# Driver5.net
KiCad netlist of a schematic drawn in Altium Designer
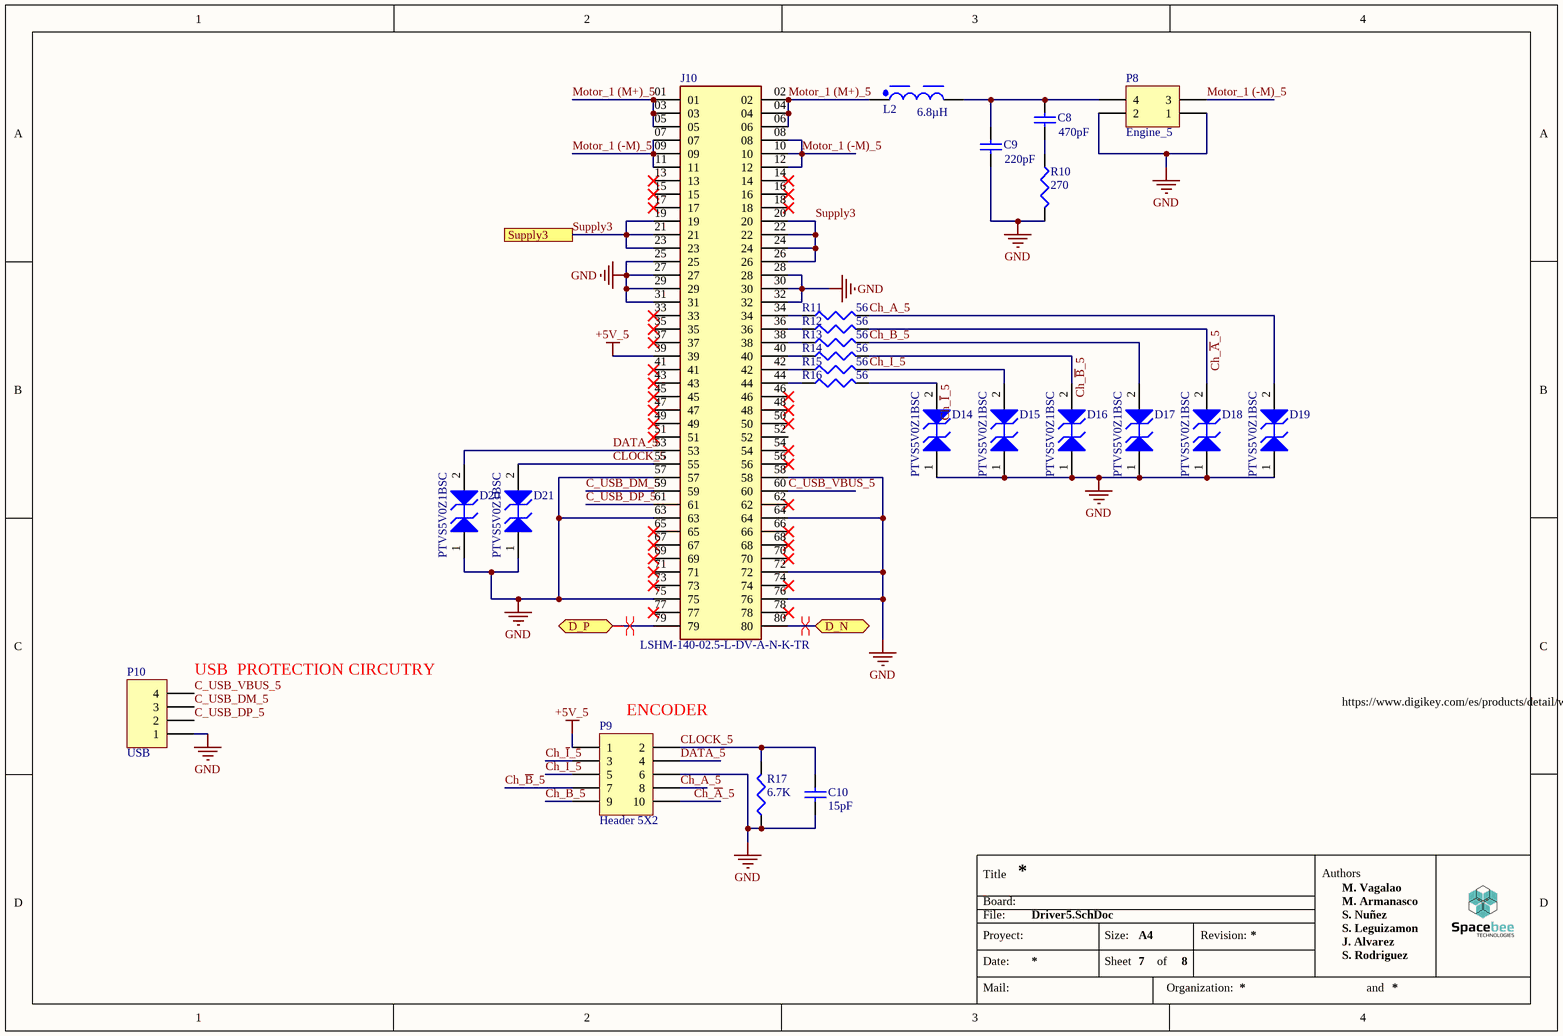
[diagram p0: Driver5.SchDoc]

(export (version "E")
  (design (tool "Eeschema 10.0.6"))
  (components
    (comp (ref "C8")
      (value "470pF")
      (footprint "1608[0603]")
      (description "Capacitor (Semiconductor SIM Model)")
      (fields (field (name "Comment") "Cap Semi") (field (name "PUBLISHER") "Altium Limited"))
      (libsource (lib "Miscellaneous Devices") (part "Cap Semi"))
    )
    (comp (ref "C9")
      (value "220pF")
      (footprint "1608[0603]")
      (description "Capacitor (Semiconductor SIM Model)")
      (fields (field (name "Comment") "Cap Semi") (field (name "PUBLISHER") "Altium Limited"))
      (libsource (lib "Miscellaneous Devices") (part "Cap Semi"))
    )
    (comp (ref "C10")
      (value "15pF")
      (footprint "6-0805_L")
      (description "Capacitor (Semiconductor SIM Model)")
      (fields (field (name "Comment") "Cap Semi") (field (name "PUBLISHER") "Altium Limited"))
      (libsource (lib "SpaceBee") (part "Cap 0805"))
    )
    (comp (ref "D14")
      (value "PTVS5V0Z1BSC")
      (footprint "SOD993B")
      (fields (field (name "MANUFACTURER") "On Semiconductor") (field (name "PARTNUMBER") "1SMB16CAT3"))
      (libsource (lib "DriverLib") (part "PTVS5V0Z1BSC"))
    )
    (comp (ref "D15")
      (value "PTVS5V0Z1BSC")
      (footprint "SOD993B")
      (fields (field (name "MANUFACTURER") "On Semiconductor") (field (name "PARTNUMBER") "1SMB16CAT3"))
      (libsource (lib "DriverLib") (part "PTVS5V0Z1BSC"))
    )
    (comp (ref "D16")
      (value "PTVS5V0Z1BSC")
      (footprint "SOD993B")
      (fields (field (name "MANUFACTURER") "On Semiconductor") (field (name "PARTNUMBER") "1SMB16CAT3"))
      (libsource (lib "DriverLib") (part "PTVS5V0Z1BSC"))
    )
    (comp (ref "D17")
      (value "PTVS5V0Z1BSC")
      (footprint "SOD993B")
      (fields (field (name "MANUFACTURER") "On Semiconductor") (field (name "PARTNUMBER") "1SMB16CAT3"))
      (libsource (lib "DriverLib") (part "PTVS5V0Z1BSC"))
    )
    (comp (ref "D18")
      (value "PTVS5V0Z1BSC")
      (footprint "SOD993B")
      (fields (field (name "MANUFACTURER") "On Semiconductor") (field (name "PARTNUMBER") "1SMB16CAT3"))
      (libsource (lib "DriverLib") (part "PTVS5V0Z1BSC"))
    )
    (comp (ref "D19")
      (value "PTVS5V0Z1BSC")
      (footprint "SOD993B")
      (fields (field (name "MANUFACTURER") "On Semiconductor") (field (name "PARTNUMBER") "1SMB16CAT3"))
      (libsource (lib "DriverLib") (part "PTVS5V0Z1BSC"))
    )
    (comp (ref "D20")
      (value "PTVS5V0Z1BSC")
      (footprint "SOD993B")
      (fields (field (name "MANUFACTURER") "On Semiconductor") (field (name "PARTNUMBER") "1SMB16CAT3"))
      (libsource (lib "DriverLib") (part "PTVS5V0Z1BSC"))
    )
    (comp (ref "D21")
      (value "PTVS5V0Z1BSC")
      (footprint "SOD993B")
      (fields (field (name "MANUFACTURER") "On Semiconductor") (field (name "PARTNUMBER") "1SMB16CAT3"))
      (libsource (lib "DriverLib") (part "PTVS5V0Z1BSC"))
    )
    (comp (ref "J10")
      (value "LSHM-140-02.5-L-DV-A-N-K-TR")
      (footprint "SAMTEC_LSHM-140-02.5-L-DV-A-N-K-TR")
      (description "LSHM - Samtec 0.50mm Razor Beam High-Speed Hermaphroditic Terminal / Socket Strip.")
      (libsource (lib "DriverLib") (part "LSHM-140-02.5-L-DV-A-N-K-TR"))
    )
    (comp (ref "L2")
      (value "6.8µH")
      (footprint "WE-XHMA_6060")
      (description "WE-XHMA SMD Power Inductor, size 1090, 6.8µH, 10.5A, 7.16mΩ")
      (fields
        (field (name "MANUFACTURER PART NUMBER") "78439369068")
        (field (name "MANUFACTURER") "Wurth Elektronik")
      )
      (libsource (lib "DriverLib") (part "78439369068"))
    )
    (comp (ref "P8")
      (value "Engine_5")
      (footprint "MOLEX_1724480004")
      (description "Header, 2-Pin, Dual row")
      (fields (field (name "PUBLISHER") "Altium Limited"))
      (libsource (lib "SpaceBee") (part "Header 2X2"))
    )
    (comp (ref "P9")
      (value "Header 5X2")
      (footprint "CONN_HIF3FC-14PA-2.54DS(71)_HIR")
      (description "Header, 5-Pin, Dual row")
      (fields (field (name "PUBLISHER") "Altium Limited"))
      (libsource (lib "DriverLib") (part "Header 5X2"))
    )
    (comp (ref "P10")
      (value "USB")
      (footprint "Header 4 SMD")
      (description "Header, 4-Pin")
      (fields (field (name "PUBLISHER") "Altium Limited"))
      (libsource (lib "SpaceBee") (part "Header 4 SMD"))
    )
    (comp (ref "R10")
      (value "270")
      (footprint "J1-0603")
      (description "Resistor")
      (fields (field (name "Comment") "Res3") (field (name "PUBLISHER") "Altium Limited"))
      (libsource (lib "Miscellaneous Devices") (part "Res3"))
    )
    (comp (ref "R11")
      (value "56")
      (footprint "J1-0603")
      (description "Resistor")
      (fields (field (name "Comment") "Res3") (field (name "PUBLISHER") "Altium Limited"))
      (libsource (lib "Miscellaneous Devices") (part "Res3"))
    )
    (comp (ref "R12")
      (value "56")
      (footprint "J1-0603")
      (description "Resistor")
      (fields (field (name "Comment") "Res3") (field (name "PUBLISHER") "Altium Limited"))
      (libsource (lib "Miscellaneous Devices") (part "Res3"))
    )
    (comp (ref "R13")
      (value "56")
      (footprint "J1-0603")
      (description "Resistor")
      (fields (field (name "Comment") "Res3") (field (name "PUBLISHER") "Altium Limited"))
      (libsource (lib "Miscellaneous Devices") (part "Res3"))
    )
    (comp (ref "R14")
      (value "56")
      (footprint "J1-0603")
      (description "Resistor")
      (fields (field (name "Comment") "Res3") (field (name "PUBLISHER") "Altium Limited"))
      (libsource (lib "Miscellaneous Devices") (part "Res3"))
    )
    (comp (ref "R15")
      (value "56")
      (footprint "J1-0603")
      (description "Resistor")
      (fields (field (name "Comment") "Res3") (field (name "PUBLISHER") "Altium Limited"))
      (libsource (lib "Miscellaneous Devices") (part "Res3"))
    )
    (comp (ref "R16")
      (value "56")
      (footprint "J1-0603")
      (description "Resistor")
      (fields (field (name "Comment") "Res3") (field (name "PUBLISHER") "Altium Limited"))
      (libsource (lib "Miscellaneous Devices") (part "Res3"))
    )
    (comp (ref "R17")
      (value "6.7K")
      (footprint "J1-0603")
      (description "Resistor")
      (fields (field (name "Comment") "Res3") (field (name "PUBLISHER") "Altium Limited"))
      (libsource (lib "Miscellaneous Devices") (part "Res3"))
    )
  )
  (nets
    (net (code "1") (name "+5V_5") (class "Default")
      (node (ref "J10") (pin "39") (pinfunction "39_39") (pintype "passive"))
      (node (ref "P9") (pin "1") (pinfunction "1_1") (pintype "passive"))
    )
    (net (code "2") (name "/CLOCK_5") (class "Default")
      (node (ref "C10") (pin "2") (pinfunction "2_2") (pintype "passive"))
      (node (ref "D21") (pin "2") (pinfunction "A2_2") (pintype "passive"))
      (node (ref "J10") (pin "55") (pinfunction "55_55") (pintype "passive"))
      (node (ref "P9") (pin "2") (pinfunction "2_2") (pintype "passive"))
      (node (ref "R17") (pin "2") (pinfunction "2_2") (pintype "passive"))
    )
    (net (code "3") (name "/C_USB_DM_5") (class "Default")
      (node (ref "J10") (pin "59") (pinfunction "59_59") (pintype "passive"))
      (node (ref "P10") (pin "3") (pinfunction "3_3") (pintype "passive"))
    )
    (net (code "4") (name "/C_USB_DP_5") (class "Default")
      (node (ref "J10") (pin "61") (pinfunction "61_61") (pintype "passive"))
      (node (ref "P10") (pin "2") (pinfunction "2_2") (pintype "passive"))
    )
    (net (code "5") (name "/C_USB_VBUS_5") (class "Default")
      (node (ref "J10") (pin "60") (pinfunction "60_60") (pintype "passive"))
      (node (ref "P10") (pin "4") (pinfunction "4_4") (pintype "passive"))
    )
    (net (code "6") (name "/Ch_A_5") (class "Default")
      (node (ref "D19") (pin "2") (pinfunction "A2_2") (pintype "passive"))
      (node (ref "P9") (pin "8") (pinfunction "8_8") (pintype "passive"))
      (node (ref "R11") (pin "2") (pinfunction "2_2") (pintype "passive"))
    )
    (net (code "7") (name "/Ch_B_5") (class "Default")
      (node (ref "D17") (pin "2") (pinfunction "A2_2") (pintype "passive"))
      (node (ref "P9") (pin "9") (pinfunction "9_9") (pintype "passive"))
      (node (ref "R13") (pin "2") (pinfunction "2_2") (pintype "passive"))
    )
    (net (code "8") (name "/Ch_I_5") (class "Default")
      (node (ref "D15") (pin "2") (pinfunction "A2_2") (pintype "passive"))
      (node (ref "P9") (pin "5") (pinfunction "5_5") (pintype "passive"))
      (node (ref "R15") (pin "2") (pinfunction "2_2") (pintype "passive"))
    )
    (net (code "9") (name "/Ch_~{A}_5") (class "Default")
      (node (ref "D18") (pin "2") (pinfunction "A2_2") (pintype "passive"))
      (node (ref "P9") (pin "10") (pinfunction "10_10") (pintype "passive"))
      (node (ref "R12") (pin "2") (pinfunction "2_2") (pintype "passive"))
    )
    (net (code "10") (name "/Ch_~{B}_5") (class "Default")
      (node (ref "D16") (pin "2") (pinfunction "A2_2") (pintype "passive"))
      (node (ref "P9") (pin "7") (pinfunction "7_7") (pintype "passive"))
      (node (ref "R14") (pin "2") (pinfunction "2_2") (pintype "passive"))
    )
    (net (code "11") (name "/Ch_~{I}_5") (class "Default")
      (node (ref "D14") (pin "2") (pinfunction "A2_2") (pintype "passive"))
      (node (ref "P9") (pin "3") (pinfunction "3_3") (pintype "passive"))
      (node (ref "R16") (pin "2") (pinfunction "2_2") (pintype "passive"))
    )
    (net (code "12") (name "/DATA_5") (class "Default")
      (node (ref "D20") (pin "2") (pinfunction "A2_2") (pintype "passive"))
      (node (ref "J10") (pin "53") (pinfunction "53_53") (pintype "passive"))
      (node (ref "P9") (pin "4") (pinfunction "4_4") (pintype "passive"))
    )
    (net (code "13") (name "/D_N") (class "Default")
      (node (ref "J10") (pin "80") (pinfunction "80_80") (pintype "passive"))
    )
    (net (code "14") (name "/D_P") (class "Default")
      (node (ref "J10") (pin "79") (pinfunction "79_79") (pintype "passive"))
    )
    (net (code "15") (name "/Motor_1 (-M)_5") (class "Default")
      (node (ref "J10") (pin "07") (pinfunction "07_07") (pintype "passive"))
      (node (ref "J10") (pin "08") (pinfunction "08_08") (pintype "passive"))
      (node (ref "J10") (pin "09") (pinfunction "09_09") (pintype "passive"))
      (node (ref "J10") (pin "10") (pinfunction "10_10") (pintype "passive"))
      (node (ref "J10") (pin "11") (pinfunction "11_11") (pintype "passive"))
      (node (ref "J10") (pin "12") (pinfunction "12_12") (pintype "passive"))
      (node (ref "P8") (pin "3") (pinfunction "3_3") (pintype "passive"))
    )
    (net (code "16") (name "/Motor_1 (M+)_5") (class "Default")
      (node (ref "J10") (pin "01") (pinfunction "01_01") (pintype "passive"))
      (node (ref "J10") (pin "02") (pinfunction "02_02") (pintype "passive"))
      (node (ref "J10") (pin "03") (pinfunction "03_03") (pintype "passive"))
      (node (ref "J10") (pin "04") (pinfunction "04_04") (pintype "passive"))
      (node (ref "J10") (pin "05") (pinfunction "05_05") (pintype "passive"))
      (node (ref "J10") (pin "06") (pinfunction "06_06") (pintype "passive"))
      (node (ref "L2") (pin "1") (pinfunction "1_1") (pintype "passive"))
    )
    (net (code "17") (name "/Supply3") (class "Default")
      (node (ref "J10") (pin "19") (pinfunction "19_19") (pintype "passive"))
      (node (ref "J10") (pin "20") (pinfunction "20_20") (pintype "passive"))
      (node (ref "J10") (pin "21") (pinfunction "21_21") (pintype "passive"))
      (node (ref "J10") (pin "22") (pinfunction "22_22") (pintype "passive"))
      (node (ref "J10") (pin "23") (pinfunction "23_23") (pintype "passive"))
      (node (ref "J10") (pin "24") (pinfunction "24_24") (pintype "passive"))
      (node (ref "J10") (pin "26") (pinfunction "26_26") (pintype "passive"))
    )
    (net (code "18") (name "GND") (class "Default")
      (node (ref "C10") (pin "1") (pinfunction "1_1") (pintype "passive"))
      (node (ref "C9") (pin "2") (pinfunction "2_2") (pintype "passive"))
      (node (ref "D14") (pin "1") (pinfunction "A1_1") (pintype "passive"))
      (node (ref "D15") (pin "1") (pinfunction "A1_1") (pintype "passive"))
      (node (ref "D16") (pin "1") (pinfunction "A1_1") (pintype "passive"))
      (node (ref "D17") (pin "1") (pinfunction "A1_1") (pintype "passive"))
      (node (ref "D18") (pin "1") (pinfunction "A1_1") (pintype "passive"))
      (node (ref "D19") (pin "1") (pinfunction "A1_1") (pintype "passive"))
      (node (ref "D20") (pin "1") (pinfunction "A1_1") (pintype "passive"))
      (node (ref "D21") (pin "1") (pinfunction "A1_1") (pintype "passive"))
      (node (ref "J10") (pin "25") (pinfunction "25_25") (pintype "passive"))
      (node (ref "J10") (pin "27") (pinfunction "27_27") (pintype "passive"))
      (node (ref "J10") (pin "28") (pinfunction "28_28") (pintype "passive"))
      (node (ref "J10") (pin "29") (pinfunction "29_29") (pintype "passive"))
      (node (ref "J10") (pin "30") (pinfunction "30_30") (pintype "passive"))
      (node (ref "J10") (pin "31") (pinfunction "31_31") (pintype "passive"))
      (node (ref "J10") (pin "32") (pinfunction "32_32") (pintype "passive"))
      (node (ref "J10") (pin "57") (pinfunction "57_57") (pintype "passive"))
      (node (ref "J10") (pin "58") (pinfunction "58_58") (pintype "passive"))
      (node (ref "J10") (pin "63") (pinfunction "63_63") (pintype "passive"))
      (node (ref "J10") (pin "64") (pinfunction "64_64") (pintype "passive"))
      (node (ref "J10") (pin "72") (pinfunction "72_72") (pintype "passive"))
      (node (ref "J10") (pin "75") (pinfunction "75_75") (pintype "passive"))
      (node (ref "J10") (pin "76") (pinfunction "76_76") (pintype "passive"))
      (node (ref "P10") (pin "1") (pinfunction "1_1") (pintype "passive"))
      (node (ref "P8") (pin "1") (pinfunction "1_1") (pintype "passive"))
      (node (ref "P8") (pin "2") (pinfunction "2_2") (pintype "passive"))
      (node (ref "P9") (pin "6") (pinfunction "6_6") (pintype "passive"))
      (node (ref "R10") (pin "2") (pinfunction "2_2") (pintype "passive"))
      (node (ref "R17") (pin "1") (pinfunction "1_1") (pintype "passive"))
    )
    (net (code "19") (name "Net-(C8-Pad1)") (class "Default")
      (node (ref "C8") (pin "1") (pinfunction "1_1") (pintype "passive"))
      (node (ref "C9") (pin "1") (pinfunction "1_1") (pintype "passive"))
      (node (ref "L2") (pin "2") (pinfunction "2_2") (pintype "passive"))
      (node (ref "P8") (pin "4") (pinfunction "4_4") (pintype "passive"))
    )
    (net (code "20") (name "Net-(C8-Pad2)") (class "Default")
      (node (ref "C8") (pin "2") (pinfunction "2_2") (pintype "passive"))
      (node (ref "R10") (pin "1") (pinfunction "1_1") (pintype "passive"))
    )
    (net (code "21") (name "Net-(J10-Pad34)") (class "Default")
      (node (ref "J10") (pin "34") (pinfunction "34_34") (pintype "passive"))
      (node (ref "R11") (pin "1") (pinfunction "1_1") (pintype "passive"))
    )
    (net (code "22") (name "Net-(J10-Pad36)") (class "Default")
      (node (ref "J10") (pin "36") (pinfunction "36_36") (pintype "passive"))
      (node (ref "R12") (pin "1") (pinfunction "1_1") (pintype "passive"))
    )
    (net (code "23") (name "Net-(J10-Pad38)") (class "Default")
      (node (ref "J10") (pin "38") (pinfunction "38_38") (pintype "passive"))
      (node (ref "R13") (pin "1") (pinfunction "1_1") (pintype "passive"))
    )
    (net (code "24") (name "Net-(J10-Pad40)") (class "Default")
      (node (ref "J10") (pin "40") (pinfunction "40_40") (pintype "passive"))
      (node (ref "R14") (pin "1") (pinfunction "1_1") (pintype "passive"))
    )
    (net (code "25") (name "Net-(J10-Pad42)") (class "Default")
      (node (ref "J10") (pin "42") (pinfunction "42_42") (pintype "passive"))
      (node (ref "R15") (pin "1") (pinfunction "1_1") (pintype "passive"))
    )
    (net (code "26") (name "Net-(J10-Pad44)") (class "Default")
      (node (ref "J10") (pin "44") (pinfunction "44_44") (pintype "passive"))
      (node (ref "R16") (pin "1") (pinfunction "1_1") (pintype "passive"))
    )
    (net (code "27") (name "unconnected-(J10-Pad13)") (class "Default")
      (node (ref "J10") (pin "13") (pinfunction "13_13") (pintype "passive+no_connect"))
    )
    (net (code "28") (name "unconnected-(J10-Pad14)") (class "Default")
      (node (ref "J10") (pin "14") (pinfunction "14_14") (pintype "passive+no_connect"))
    )
    (net (code "29") (name "unconnected-(J10-Pad15)") (class "Default")
      (node (ref "J10") (pin "15") (pinfunction "15_15") (pintype "passive+no_connect"))
    )
    (net (code "30") (name "unconnected-(J10-Pad16)") (class "Default")
      (node (ref "J10") (pin "16") (pinfunction "16_16") (pintype "passive+no_connect"))
    )
    (net (code "31") (name "unconnected-(J10-Pad17)") (class "Default")
      (node (ref "J10") (pin "17") (pinfunction "17_17") (pintype "passive+no_connect"))
    )
    (net (code "32") (name "unconnected-(J10-Pad18)") (class "Default")
      (node (ref "J10") (pin "18") (pinfunction "18_18") (pintype "passive+no_connect"))
    )
    (net (code "33") (name "unconnected-(J10-Pad33)") (class "Default")
      (node (ref "J10") (pin "33") (pinfunction "33_33") (pintype "passive+no_connect"))
    )
    (net (code "34") (name "unconnected-(J10-Pad35)") (class "Default")
      (node (ref "J10") (pin "35") (pinfunction "35_35") (pintype "passive+no_connect"))
    )
    (net (code "35") (name "unconnected-(J10-Pad37)") (class "Default")
      (node (ref "J10") (pin "37") (pinfunction "37_37") (pintype "passive+no_connect"))
    )
    (net (code "36") (name "unconnected-(J10-Pad41)") (class "Default")
      (node (ref "J10") (pin "41") (pinfunction "41_41") (pintype "passive+no_connect"))
    )
    (net (code "37") (name "unconnected-(J10-Pad43)") (class "Default")
      (node (ref "J10") (pin "43") (pinfunction "43_43") (pintype "passive+no_connect"))
    )
    (net (code "38") (name "unconnected-(J10-Pad45)") (class "Default")
      (node (ref "J10") (pin "45") (pinfunction "45_45") (pintype "passive+no_connect"))
    )
    (net (code "39") (name "unconnected-(J10-Pad46)") (class "Default")
      (node (ref "J10") (pin "46") (pinfunction "46_46") (pintype "passive+no_connect"))
    )
    (net (code "40") (name "unconnected-(J10-Pad47)") (class "Default")
      (node (ref "J10") (pin "47") (pinfunction "47_47") (pintype "passive+no_connect"))
    )
    (net (code "41") (name "unconnected-(J10-Pad48)") (class "Default")
      (node (ref "J10") (pin "48") (pinfunction "48_48") (pintype "passive+no_connect"))
    )
    (net (code "42") (name "unconnected-(J10-Pad49)") (class "Default")
      (node (ref "J10") (pin "49") (pinfunction "49_49") (pintype "passive+no_connect"))
    )
    (net (code "43") (name "unconnected-(J10-Pad50)") (class "Default")
      (node (ref "J10") (pin "50") (pinfunction "50_50") (pintype "passive+no_connect"))
    )
    (net (code "44") (name "unconnected-(J10-Pad51)") (class "Default")
      (node (ref "J10") (pin "51") (pinfunction "51_51") (pintype "passive+no_connect"))
    )
    (net (code "45") (name "unconnected-(J10-Pad52)") (class "Default")
      (node (ref "J10") (pin "52") (pinfunction "52_52") (pintype "passive"))
    )
    (net (code "46") (name "unconnected-(J10-Pad54)") (class "Default")
      (node (ref "J10") (pin "54") (pinfunction "54_54") (pintype "passive+no_connect"))
    )
    (net (code "47") (name "unconnected-(J10-Pad56)") (class "Default")
      (node (ref "J10") (pin "56") (pinfunction "56_56") (pintype "passive+no_connect"))
    )
    (net (code "48") (name "unconnected-(J10-Pad62)") (class "Default")
      (node (ref "J10") (pin "62") (pinfunction "62_62") (pintype "passive+no_connect"))
    )
    (net (code "49") (name "unconnected-(J10-Pad65)") (class "Default")
      (node (ref "J10") (pin "65") (pinfunction "65_65") (pintype "passive+no_connect"))
    )
    (net (code "50") (name "unconnected-(J10-Pad66)") (class "Default")
      (node (ref "J10") (pin "66") (pinfunction "66_66") (pintype "passive+no_connect"))
    )
    (net (code "51") (name "unconnected-(J10-Pad67)") (class "Default")
      (node (ref "J10") (pin "67") (pinfunction "67_67") (pintype "passive+no_connect"))
    )
    (net (code "52") (name "unconnected-(J10-Pad68)") (class "Default")
      (node (ref "J10") (pin "68") (pinfunction "68_68") (pintype "passive+no_connect"))
    )
    (net (code "53") (name "unconnected-(J10-Pad69)") (class "Default")
      (node (ref "J10") (pin "69") (pinfunction "69_69") (pintype "passive+no_connect"))
    )
    (net (code "54") (name "unconnected-(J10-Pad70)") (class "Default")
      (node (ref "J10") (pin "70") (pinfunction "70_70") (pintype "passive+no_connect"))
    )
    (net (code "55") (name "unconnected-(J10-Pad71)") (class "Default")
      (node (ref "J10") (pin "71") (pinfunction "71_71") (pintype "passive+no_connect"))
    )
    (net (code "56") (name "unconnected-(J10-Pad73)") (class "Default")
      (node (ref "J10") (pin "73") (pinfunction "73_73") (pintype "passive+no_connect"))
    )
    (net (code "57") (name "unconnected-(J10-Pad74)") (class "Default")
      (node (ref "J10") (pin "74") (pinfunction "74_74") (pintype "passive+no_connect"))
    )
    (net (code "58") (name "unconnected-(J10-Pad77)") (class "Default")
      (node (ref "J10") (pin "77") (pinfunction "77_77") (pintype "passive+no_connect"))
    )
    (net (code "59") (name "unconnected-(J10-Pad78)") (class "Default")
      (node (ref "J10") (pin "78") (pinfunction "78_78") (pintype "passive+no_connect"))
    )
  )
)
